# UpTo11_MotherBoard.net
KiCad netlist of a schematic drawn in EAGLE
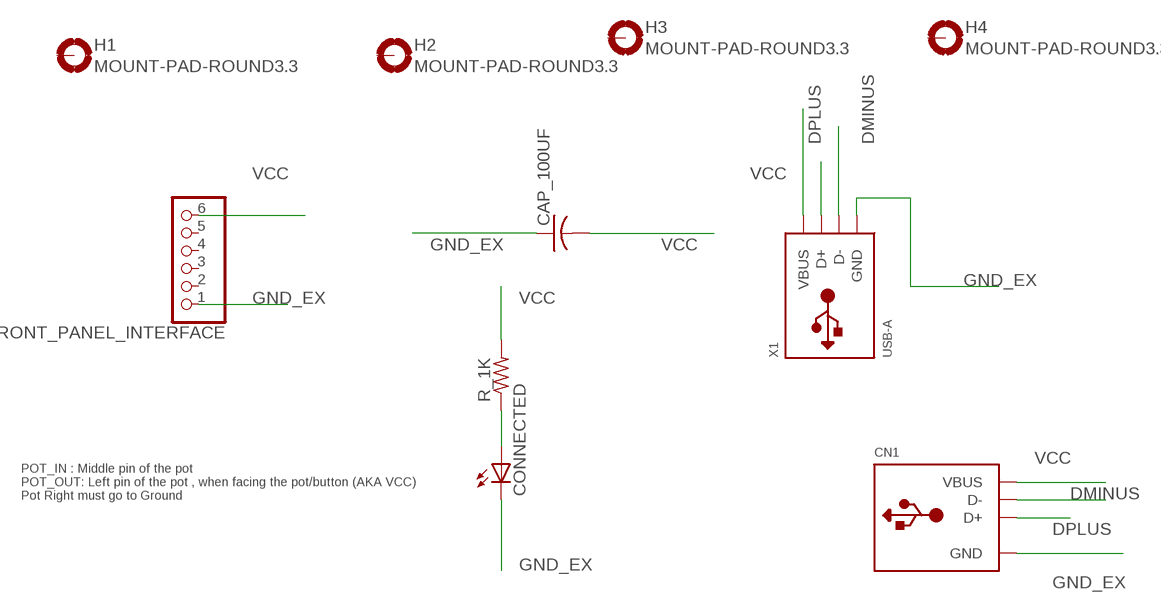
[diagram p0: schematic, sheet 1]

(export (version "E")
  (design (tool "Eeschema 10.0.6"))
  (components
    (comp (ref "CAP_100UF")
      (value "C-US025-030X050")
      (footprint "eagle-import:C025-030X050")
      (libsource (lib "eagle-import") (part "C-US025-030X050"))
    )
    (comp (ref "CN1")
      (value "USB_TYPEAPTHFML")
      (footprint "eagle-import:USB_HOST-PTH")
      (libsource (lib "eagle-import") (part "USB_TYPEAPTHFML"))
    )
    (comp (ref "CONNECTED")
      (value "LEDSMT1206")
      (footprint "eagle-import:1206")
      (libsource (lib "eagle-import") (part "LEDSMT1206"))
    )
    (comp (ref "FRONT_PANEL_INTERFACE")
      (value "PINHD-1X6")
      (footprint "eagle-import:1X06")
      (libsource (lib "eagle-import") (part "PINHD-1X6"))
    )
    (comp (ref "H1")
      (value "MOUNT-PAD-ROUND3.3")
      (footprint "eagle-import:3,3-PAD")
      (libsource (lib "eagle-import") (part "MOUNT-PAD-ROUND3.3"))
    )
    (comp (ref "H2")
      (value "MOUNT-PAD-ROUND3.3")
      (footprint "eagle-import:3,3-PAD")
      (libsource (lib "eagle-import") (part "MOUNT-PAD-ROUND3.3"))
    )
    (comp (ref "H3")
      (value "MOUNT-PAD-ROUND3.3")
      (footprint "eagle-import:3,3-PAD")
      (libsource (lib "eagle-import") (part "MOUNT-PAD-ROUND3.3"))
    )
    (comp (ref "H4")
      (value "MOUNT-PAD-ROUND3.3")
      (footprint "eagle-import:3,3-PAD")
      (libsource (lib "eagle-import") (part "MOUNT-PAD-ROUND3.3"))
    )
    (comp (ref "R_1K")
      (value "R-US_R1206")
      (footprint "eagle-import:R1206")
      (libsource (lib "eagle-import") (part "R-US_R1206"))
    )
    (comp (ref "X1")
      (value "USB-A")
      (footprint "eagle-import:MOLEX_480371000")
      (libsource (lib "eagle-import") (part "USB-A"))
    )
  )
  (nets
    (net (code "1") (name "/DMINUS") (class "Default")
      (node (ref "CN1") (pin "D-") (pinfunction "D-_D-") (pintype "bidirectional"))
      (node (ref "X1") (pin "2") (pinfunction "D-_2") (pintype "bidirectional"))
    )
    (net (code "2") (name "/DPLUS") (class "Default")
      (node (ref "CN1") (pin "D+") (pinfunction "D+_D+") (pintype "bidirectional"))
      (node (ref "X1") (pin "3") (pinfunction "D+_3") (pintype "bidirectional"))
    )
    (net (code "3") (name "/GND_EX") (class "Default")
      (node (ref "CAP_100UF") (pin "1") (pinfunction "1_1") (pintype "passive"))
      (node (ref "CN1") (pin "GND") (pinfunction "GND_GND") (pintype "power_in"))
      (node (ref "CONNECTED") (pin "C") (pinfunction "C_C") (pintype "passive"))
      (node (ref "FRONT_PANEL_INTERFACE") (pin "1") (pinfunction "1_1") (pintype "passive"))
      (node (ref "X1") (pin "4") (pinfunction "GND_4") (pintype "power_in"))
    )
    (net (code "4") (name "/VCC") (class "Default")
      (node (ref "CAP_100UF") (pin "2") (pinfunction "2_2") (pintype "passive"))
      (node (ref "CN1") (pin "VBUS") (pinfunction "VBUS_VBUS") (pintype "power_in"))
      (node (ref "FRONT_PANEL_INTERFACE") (pin "6") (pinfunction "6_6") (pintype "passive"))
      (node (ref "R_1K") (pin "2") (pinfunction "2_2") (pintype "passive"))
      (node (ref "X1") (pin "1") (pinfunction "VBUS_1") (pintype "power_in"))
    )
    (net (code "5") (name "Net-(CONNECTED-PadA)") (class "Default")
      (node (ref "CONNECTED") (pin "A") (pinfunction "A_A") (pintype "passive"))
      (node (ref "R_1K") (pin "1") (pinfunction "1_1") (pintype "passive"))
    )
    (net (code "6") (name "unconnected-(FRONT_PANEL_INTERFACE-Pad2)") (class "Default")
      (node (ref "FRONT_PANEL_INTERFACE") (pin "2") (pinfunction "2_2") (pintype "passive"))
    )
    (net (code "7") (name "unconnected-(FRONT_PANEL_INTERFACE-Pad3)") (class "Default")
      (node (ref "FRONT_PANEL_INTERFACE") (pin "3") (pinfunction "3_3") (pintype "passive"))
    )
    (net (code "8") (name "unconnected-(FRONT_PANEL_INTERFACE-Pad4)") (class "Default")
      (node (ref "FRONT_PANEL_INTERFACE") (pin "4") (pinfunction "4_4") (pintype "passive"))
    )
    (net (code "9") (name "unconnected-(FRONT_PANEL_INTERFACE-Pad5)") (class "Default")
      (node (ref "FRONT_PANEL_INTERFACE") (pin "5") (pinfunction "5_5") (pintype "passive"))
    )
    (net (code "10") (name "unconnected-(H1-MOUNT-PadB3,3)") (class "Default")
      (node (ref "H1") (pin "B3,3") (pinfunction "MOUNT_B3,3") (pintype "passive"))
    )
    (net (code "11") (name "unconnected-(H2-MOUNT-PadB3,3)") (class "Default")
      (node (ref "H2") (pin "B3,3") (pinfunction "MOUNT_B3,3") (pintype "passive"))
    )
    (net (code "12") (name "unconnected-(H3-MOUNT-PadB3,3)") (class "Default")
      (node (ref "H3") (pin "B3,3") (pinfunction "MOUNT_B3,3") (pintype "passive"))
    )
    (net (code "13") (name "unconnected-(H4-MOUNT-PadB3,3)") (class "Default")
      (node (ref "H4") (pin "B3,3") (pinfunction "MOUNT_B3,3") (pintype "passive"))
    )
  )
)
